# radio.net
KiCad netlist of a schematic drawn in EAGLE
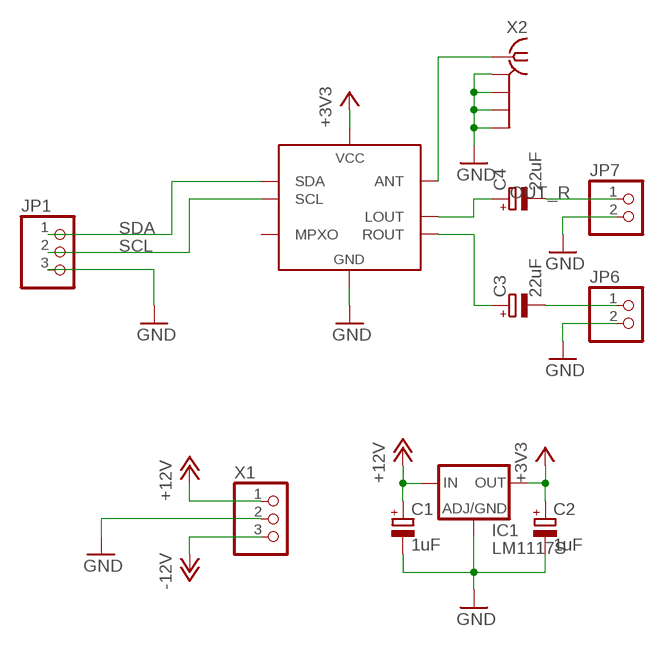
[diagram p0: schematic, sheet 1]

(export (version "E")
  (design (tool "Eeschema 10.0.6"))
  (components
    (comp (ref "C1")
      (value "1uF")
      (footprint "eagle-import:SMC_A")
      (libsource (lib "eagle-import") (part "CPOL-EUSMD"))
    )
    (comp (ref "C2")
      (value "1uF")
      (footprint "eagle-import:SMC_A")
      (libsource (lib "eagle-import") (part "CPOL-EUSMD"))
    )
    (comp (ref "C3")
      (value "22uF")
      (footprint "eagle-import:PANASONIC_D")
      (libsource (lib "eagle-import") (part "CPOL-EUD"))
    )
    (comp (ref "C4")
      (value "22uF")
      (footprint "eagle-import:PANASONIC_D")
      (libsource (lib "eagle-import") (part "CPOL-EUD"))
    )
    (comp (ref "IC1")
      (value "LM1117S")
      (footprint "eagle-import:SOT223")
      (libsource (lib "eagle-import") (part "LM1117S"))
    )
    (comp (ref "JP1")
      (value "PINHD-1X3180")
      (footprint "eagle-import:1X03")
      (libsource (lib "eagle-import") (part "PINHD-1X3180"))
    )
    (comp (ref "JP6")
      (value "PINHD-1X2")
      (footprint "eagle-import:1X02")
      (libsource (lib "eagle-import") (part "PINHD-1X2"))
    )
    (comp (ref "JP7")
      (value "PINHD-1X2")
      (footprint "eagle-import:1X02")
      (libsource (lib "eagle-import") (part "PINHD-1X2"))
    )
    (comp (ref "U1")
      (value "TEA5767")
      (footprint "eagle-import:TEA5767")
      (libsource (lib "eagle-import") (part "TEA5767"))
    )
    (comp (ref "X1")
      (value "22-23-2031")
      (footprint "eagle-import:22-23-2031")
      (libsource (lib "eagle-import") (part "22-23-2031"))
    )
    (comp (ref "X2")
      (value "BU-SMA-V")
      (footprint "eagle-import:BU-SMA-V")
      (libsource (lib "eagle-import") (part "BU-SMA-V"))
    )
  )
  (nets
    (net (code "1") (name "+3V3") (class "Default")
      (node (ref "C2") (pin "+") (pinfunction "+_+") (pintype "passive"))
      (node (ref "IC1") (pin "2") (pinfunction "OUT_2") (pintype "passive"))
      (node (ref "IC1") (pin "4") (pinfunction "OUT_4") (pintype "passive"))
      (node (ref "U1") (pin "5") (pinfunction "VCC_5") (pintype "bidirectional"))
    )
    (net (code "2") (name "+12V") (class "Default")
      (node (ref "C1") (pin "+") (pinfunction "+_+") (pintype "passive"))
      (node (ref "IC1") (pin "3") (pinfunction "IN_3") (pintype "input"))
      (node (ref "X1") (pin "1") (pinfunction "1_1") (pintype "passive"))
    )
    (net (code "3") (name "-12V") (class "Default")
      (node (ref "X1") (pin "3") (pinfunction "3_3") (pintype "passive"))
    )
    (net (code "4") (name "/OUT_R") (class "Default")
      (node (ref "C4") (pin "+") (pinfunction "+_+") (pintype "passive"))
      (node (ref "U1") (pin "8") (pinfunction "LOUT_8") (pintype "bidirectional"))
    )
    (net (code "5") (name "/SCL") (class "Default")
      (node (ref "JP1") (pin "2") (pinfunction "2_2") (pintype "passive"))
      (node (ref "U1") (pin "2") (pinfunction "SCL_2") (pintype "bidirectional"))
    )
    (net (code "6") (name "/SDA") (class "Default")
      (node (ref "JP1") (pin "1") (pinfunction "1_1") (pintype "passive"))
      (node (ref "U1") (pin "1") (pinfunction "SDA_1") (pintype "bidirectional"))
    )
    (net (code "7") (name "GND") (class "Default")
      (node (ref "C1") (pin "-") (pinfunction "-_-") (pintype "passive"))
      (node (ref "C2") (pin "-") (pinfunction "-_-") (pintype "passive"))
      (node (ref "IC1") (pin "1") (pinfunction "ADJ_1") (pintype "input"))
      (node (ref "JP1") (pin "3") (pinfunction "3_3") (pintype "passive"))
      (node (ref "JP6") (pin "2") (pinfunction "2_2") (pintype "passive"))
      (node (ref "JP7") (pin "2") (pinfunction "2_2") (pintype "passive"))
      (node (ref "U1") (pin "3") (pinfunction "GND_3") (pintype "bidirectional"))
      (node (ref "U1") (pin "6") (pinfunction "GND_6") (pintype "bidirectional"))
      (node (ref "X1") (pin "2") (pinfunction "2_2") (pintype "passive"))
      (node (ref "X2") (pin "2") (pinfunction "GND1_2") (pintype "power_in"))
      (node (ref "X2") (pin "3") (pinfunction "GND2_3") (pintype "power_in"))
      (node (ref "X2") (pin "4") (pinfunction "GND3_4") (pintype "power_in"))
      (node (ref "X2") (pin "5") (pinfunction "GND4_5") (pintype "power_in"))
    )
    (net (code "8") (name "Net-(C3-Pad-)") (class "Default")
      (node (ref "C3") (pin "-") (pinfunction "-_-") (pintype "passive"))
      (node (ref "JP6") (pin "1") (pinfunction "1_1") (pintype "passive"))
    )
    (net (code "9") (name "Net-(C4-Pad-)") (class "Default")
      (node (ref "C4") (pin "-") (pinfunction "-_-") (pintype "passive"))
      (node (ref "JP7") (pin "1") (pinfunction "1_1") (pintype "passive"))
    )
    (net (code "10") (name "Net-(U1-ANT)") (class "Default")
      (node (ref "U1") (pin "10") (pinfunction "ANT_10") (pintype "bidirectional"))
      (node (ref "X2") (pin "1") (pinfunction "1_1") (pintype "passive"))
    )
    (net (code "11") (name "Net-(U1-ROUT)") (class "Default")
      (node (ref "C3") (pin "+") (pinfunction "+_+") (pintype "passive"))
      (node (ref "U1") (pin "7") (pinfunction "ROUT_7") (pintype "bidirectional"))
    )
    (net (code "12") (name "unconnected-(U1-MPXO-Pad9)") (class "Default")
      (node (ref "U1") (pin "9") (pinfunction "MPXO_9") (pintype "bidirectional"))
    )
  )
)
